# LEDs.net
KiCad netlist of a schematic drawn in Altium Designer
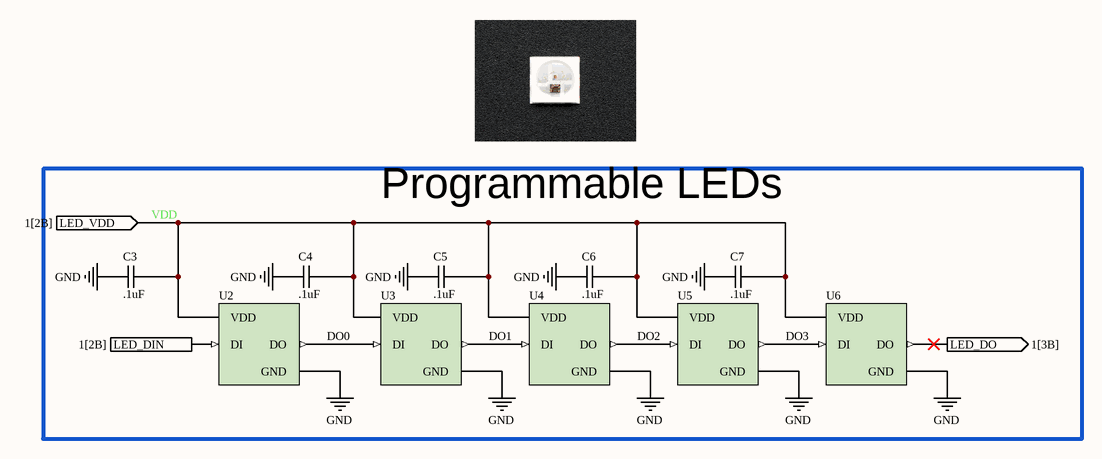
[diagram p0: LEDs.SchDoc]

(export (version "E")
  (design (tool "Eeschema 10.0.6"))
  (components
    (comp (ref "C3")
      (value ".1uF")
      (footprint "PCB-CAP-SMD-0603")
      (description "Generic (no part number) 0603 surface mount capacitor")
      (fields (field (name "Comment") "CAP-SMD-0603"))
      (libsource (lib "Animal Inspired Movement and Robotics Lab (AIMRL)") (part "SCH-CAP-SMD-0603"))
    )
    (comp (ref "C4")
      (value ".1uF")
      (footprint "PCB-CAP-SMD-0603")
      (description "Generic (no part number) 0603 surface mount capacitor")
      (fields (field (name "Comment") "CAP-SMD-0603"))
      (libsource (lib "Animal Inspired Movement and Robotics Lab (AIMRL)") (part "SCH-CAP-SMD-0603"))
    )
    (comp (ref "C5")
      (value ".1uF")
      (footprint "PCB-CAP-SMD-0603")
      (description "Generic (no part number) 0603 surface mount capacitor")
      (fields (field (name "Comment") "CAP-SMD-0603"))
      (libsource (lib "Animal Inspired Movement and Robotics Lab (AIMRL)") (part "SCH-CAP-SMD-0603"))
    )
    (comp (ref "C6")
      (value ".1uF")
      (footprint "PCB-CAP-SMD-0603")
      (description "Generic (no part number) 0603 surface mount capacitor")
      (fields (field (name "Comment") "CAP-SMD-0603"))
      (libsource (lib "Animal Inspired Movement and Robotics Lab (AIMRL)") (part "SCH-CAP-SMD-0603"))
    )
    (comp (ref "C7")
      (value ".1uF")
      (footprint "PCB-CAP-SMD-0603")
      (description "Generic (no part number) 0603 surface mount capacitor")
      (fields (field (name "Comment") "CAP-SMD-0603"))
      (libsource (lib "Animal Inspired Movement and Robotics Lab (AIMRL)") (part "SCH-CAP-SMD-0603"))
    )
    (comp (ref "U2")
      (value "LED-RGB-SK6812B-3535")
      (footprint "PCB-SK6812B-3535-SMD-3.5X3.7MM")
      (description "3.5x3.7x1.1 mm 0.2W Intelligent external control surface")
      (libsource (lib "Animal Inspired Movement and Robotics Lab (AIMRL)") (part "SCH-SK6812B-3535"))
    )
    (comp (ref "U3")
      (value "LED-RGB-SK6812B-3535")
      (footprint "PCB-SK6812B-3535-SMD-3.5X3.7MM")
      (description "3.5x3.7x1.1 mm 0.2W Intelligent external control surface")
      (libsource (lib "Animal Inspired Movement and Robotics Lab (AIMRL)") (part "SCH-SK6812B-3535"))
    )
    (comp (ref "U4")
      (value "LED-RGB-SK6812B-3535")
      (footprint "PCB-SK6812B-3535-SMD-3.5X3.7MM")
      (description "3.5x3.7x1.1 mm 0.2W Intelligent external control surface")
      (libsource (lib "Animal Inspired Movement and Robotics Lab (AIMRL)") (part "SCH-SK6812B-3535"))
    )
    (comp (ref "U5")
      (value "LED-RGB-SK6812B-3535")
      (footprint "PCB-SK6812B-3535-SMD-3.5X3.7MM")
      (description "3.5x3.7x1.1 mm 0.2W Intelligent external control surface")
      (libsource (lib "Animal Inspired Movement and Robotics Lab (AIMRL)") (part "SCH-SK6812B-3535"))
    )
    (comp (ref "U6")
      (value "LED-RGB-SK6812B-3535")
      (footprint "PCB-SK6812B-3535-SMD-3.5X3.7MM")
      (description "3.5x3.7x1.1 mm 0.2W Intelligent external control surface")
      (libsource (lib "Animal Inspired Movement and Robotics Lab (AIMRL)") (part "SCH-SK6812B-3535"))
    )
  )
  (nets
    (net (code "1") (name "/DO0") (class "Default")
      (node (ref "U2") (pin "3") (pinfunction "DO_3") (pintype "output"))
      (node (ref "U3") (pin "1") (pinfunction "DI_1") (pintype "input"))
    )
    (net (code "2") (name "/DO1") (class "Default")
      (node (ref "U3") (pin "3") (pinfunction "DO_3") (pintype "output"))
      (node (ref "U4") (pin "1") (pinfunction "DI_1") (pintype "input"))
    )
    (net (code "3") (name "/DO2") (class "Default")
      (node (ref "U4") (pin "3") (pinfunction "DO_3") (pintype "output"))
      (node (ref "U5") (pin "1") (pinfunction "DI_1") (pintype "input"))
    )
    (net (code "4") (name "/DO3") (class "Default")
      (node (ref "U5") (pin "3") (pinfunction "DO_3") (pintype "output"))
      (node (ref "U6") (pin "1") (pinfunction "DI_1") (pintype "input"))
    )
    (net (code "5") (name "/LED_DIN") (class "Default")
      (node (ref "U2") (pin "1") (pinfunction "DI_1") (pintype "input"))
    )
    (net (code "6") (name "/LED_DO") (class "Default")
      (node (ref "U6") (pin "3") (pinfunction "DO_3") (pintype "output+no_connect"))
    )
    (net (code "7") (name "/VDD") (class "Default")
      (node (ref "C3") (pin "2") (pinfunction "2_2") (pintype "passive"))
      (node (ref "C4") (pin "2") (pinfunction "2_2") (pintype "passive"))
      (node (ref "C5") (pin "2") (pinfunction "2_2") (pintype "passive"))
      (node (ref "C6") (pin "2") (pinfunction "2_2") (pintype "passive"))
      (node (ref "C7") (pin "2") (pinfunction "2_2") (pintype "passive"))
      (node (ref "U2") (pin "2") (pinfunction "VDD_2") (pintype "power_in"))
      (node (ref "U3") (pin "2") (pinfunction "VDD_2") (pintype "power_in"))
      (node (ref "U4") (pin "2") (pinfunction "VDD_2") (pintype "power_in"))
      (node (ref "U5") (pin "2") (pinfunction "VDD_2") (pintype "power_in"))
      (node (ref "U6") (pin "2") (pinfunction "VDD_2") (pintype "power_in"))
    )
    (net (code "8") (name "GND") (class "Default")
      (node (ref "C3") (pin "1") (pinfunction "1_1") (pintype "passive"))
      (node (ref "C4") (pin "1") (pinfunction "1_1") (pintype "passive"))
      (node (ref "C5") (pin "1") (pinfunction "1_1") (pintype "passive"))
      (node (ref "C6") (pin "1") (pinfunction "1_1") (pintype "passive"))
      (node (ref "C7") (pin "1") (pinfunction "1_1") (pintype "passive"))
      (node (ref "U2") (pin "4") (pinfunction "GND_4") (pintype "power_in"))
      (node (ref "U3") (pin "4") (pinfunction "GND_4") (pintype "power_in"))
      (node (ref "U4") (pin "4") (pinfunction "GND_4") (pintype "power_in"))
      (node (ref "U5") (pin "4") (pinfunction "GND_4") (pintype "power_in"))
      (node (ref "U6") (pin "4") (pinfunction "GND_4") (pintype "power_in"))
    )
  )
)
